# spice_test.net
KiCad netlist of a schematic drawn in EAGLE
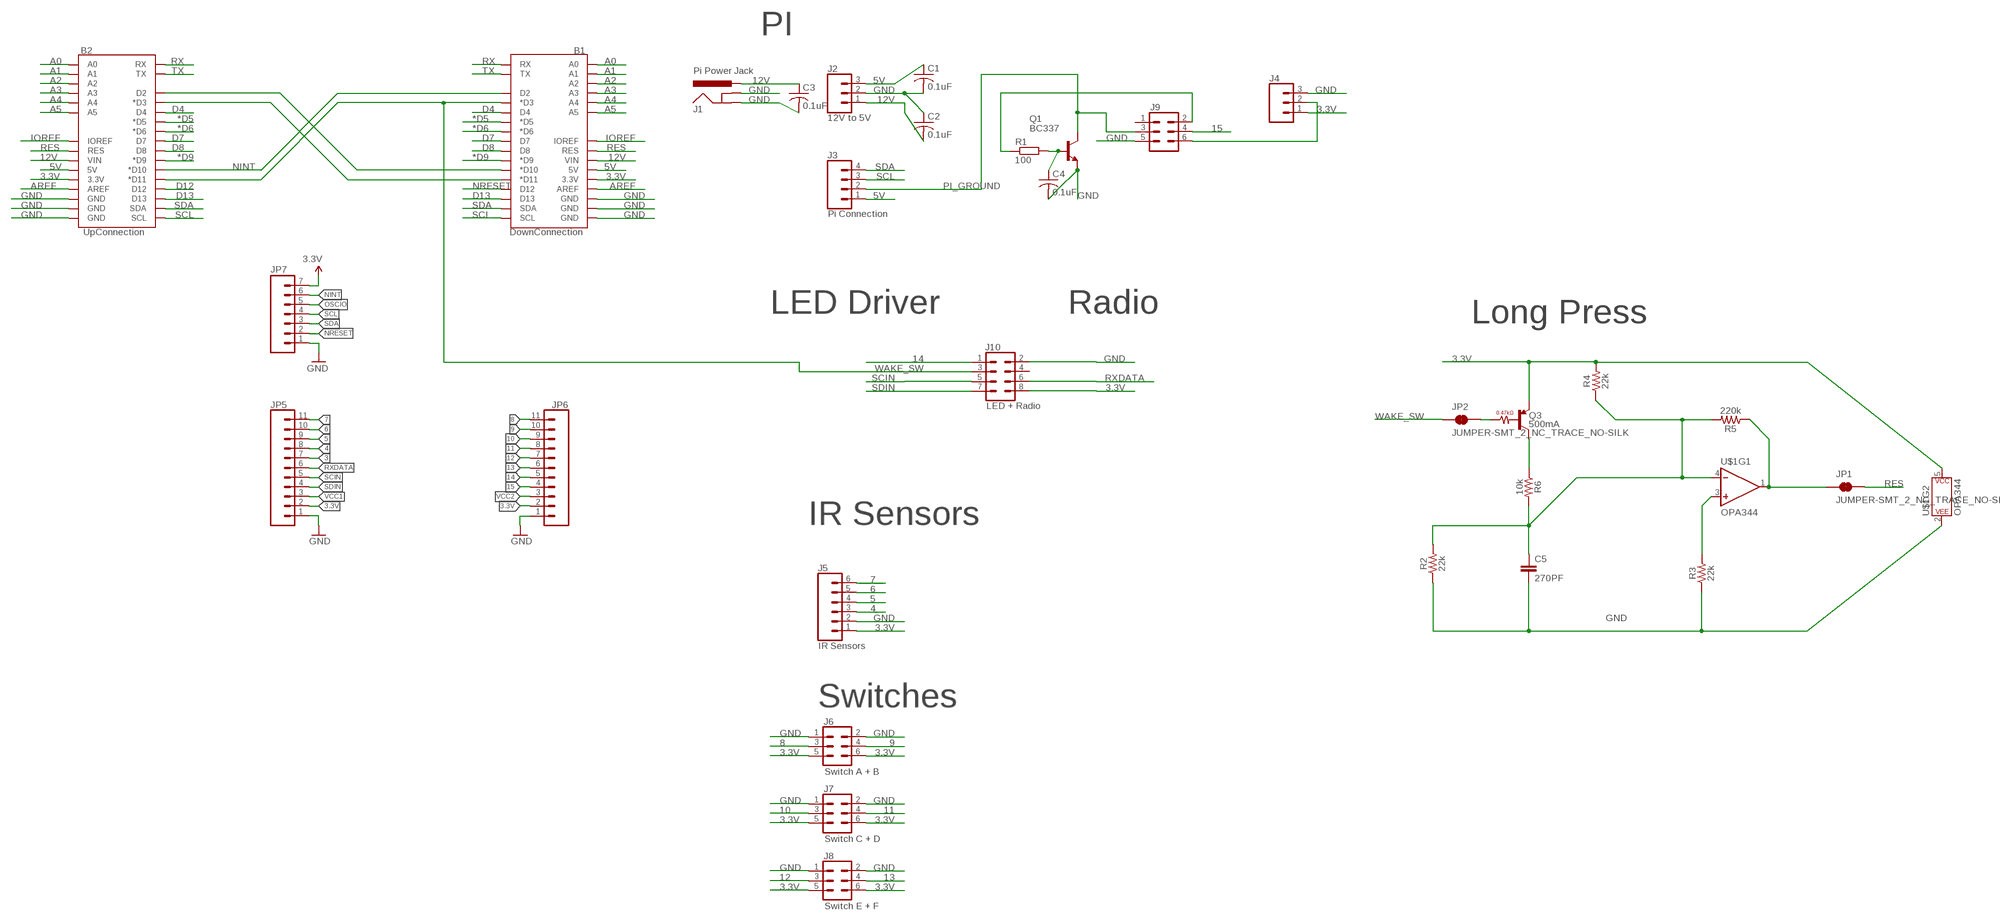
[diagram p0: schematic, sheet 1]

(export (version "E")
  (design (tool "Eeschema 10.0.6"))
  (components
    (comp (ref "B1")
      (value "DownConnection")
      (footprint "eagle-import:UNO_R3_SHIELD_NOLABELS")
      (libsource (lib "eagle-import") (part "ARDUINO_UNO_R3_SHIELDNOLABELS"))
    )
    (comp (ref "B2")
      (value "UpConnection")
      (footprint "eagle-import:UNO_R3_SHIELD_NOLABELS")
      (libsource (lib "eagle-import") (part "ARDUINO_UNO_R3_SHIELDNOLABELS"))
    )
    (comp (ref "C1")
      (value "0.1uF")
      (footprint "eagle-import:C025-024X044")
      (libsource (lib "eagle-import") (part "C-US025-024X044"))
    )
    (comp (ref "C2")
      (value "0.1uF")
      (footprint "eagle-import:C025-024X044")
      (libsource (lib "eagle-import") (part "C-US025-024X044"))
    )
    (comp (ref "C3")
      (value "0.1uF")
      (footprint "eagle-import:C025-024X044")
      (libsource (lib "eagle-import") (part "C-US025-024X044"))
    )
    (comp (ref "C4")
      (value "0.1uF")
      (footprint "eagle-import:C025-024X044")
      (libsource (lib "eagle-import") (part "C-US025-024X044"))
    )
    (comp (ref "C5")
      (value "270PF")
      (footprint "eagle-import:0603")
      (fields (field (name "SPICEPREFIX") "C"))
      (libsource (lib "eagle-import") (part "270PF-0603-50V-5%"))
    )
    (comp (ref "J1")
      (value "Pi Power Jack")
      (footprint "eagle-import:POWER_JACK_PTH_BREAD")
      (libsource (lib "eagle-import") (part "POWER_JACKPTH_BREAD"))
    )
    (comp (ref "J2")
      (value "12V to 5V")
      (footprint "eagle-import:1X03")
      (libsource (lib "eagle-import") (part "CONN_03"))
    )
    (comp (ref "J3")
      (value "Pi Connection")
      (footprint "eagle-import:1X04")
      (libsource (lib "eagle-import") (part "CONN_04"))
    )
    (comp (ref "J4")
      (value "CONN_03")
      (footprint "eagle-import:1X03")
      (libsource (lib "eagle-import") (part "CONN_03"))
    )
    (comp (ref "J5")
      (value "IR Sensors")
      (footprint "eagle-import:1X06")
      (libsource (lib "eagle-import") (part "CONN_06SILK_FEMALE_PTH"))
    )
    (comp (ref "J6")
      (value "Switch A + B")
      (footprint "eagle-import:2X3")
      (libsource (lib "eagle-import") (part "CONN_03X2FEMALE"))
    )
    (comp (ref "J7")
      (value "Switch C + D")
      (footprint "eagle-import:2X3")
      (libsource (lib "eagle-import") (part "CONN_03X2FEMALE"))
    )
    (comp (ref "J8")
      (value "Switch E + F")
      (footprint "eagle-import:2X3")
      (libsource (lib "eagle-import") (part "CONN_03X2FEMALE"))
    )
    (comp (ref "J9")
      (value "CONN_03X2NO_SILK")
      (footprint "eagle-import:2X3-NS")
      (libsource (lib "eagle-import") (part "CONN_03X2NO_SILK"))
    )
    (comp (ref "J10")
      (value "LED + Radio")
      (footprint "eagle-import:2X4")
      (libsource (lib "eagle-import") (part "CONN_04X2"))
    )
    (comp (ref "JP1")
      (value "JUMPER-SMT_2_NC_TRACE_NO-SILK")
      (footprint "eagle-import:SMT-JUMPER_2_NC_TRACE_NO-SILK")
      (fields (field (name "SPICEPREFIX") "B"))
      (libsource (lib "eagle-import") (part "JUMPER-SMT_2_NC_TRACE_NO-SILK"))
    )
    (comp (ref "JP2")
      (value "JUMPER-SMT_2_NC_TRACE_NO-SILK")
      (footprint "eagle-import:SMT-JUMPER_2_NC_TRACE_NO-SILK")
      (fields (field (name "SPICEPREFIX") "B"))
      (libsource (lib "eagle-import") (part "JUMPER-SMT_2_NC_TRACE_NO-SILK"))
    )
    (comp (ref "JP5")
      (value "CONN_11")
      (footprint "eagle-import:1X11")
      (libsource (lib "eagle-import") (part "CONN_11"))
    )
    (comp (ref "JP6")
      (value "CONN_11")
      (footprint "eagle-import:1X11")
      (libsource (lib "eagle-import") (part "CONN_11"))
    )
    (comp (ref "JP7")
      (value "M07")
      (footprint "eagle-import:1X07")
      (libsource (lib "eagle-import") (part "M07"))
    )
    (comp (ref "Q1")
      (value "BC337")
      (footprint "eagle-import:TO92")
      (libsource (lib "eagle-import") (part "BC337"))
    )
    (comp (ref "Q3")
      (value "500mA")
      (footprint "eagle-import:SOT23-3")
      (fields (field (name "SPICEPREFIX") "Q"))
      (libsource (lib "eagle-import") (part "TRANS_PNP_RES-DDTB142TC"))
    )
    (comp (ref "R1")
      (value "100")
      (footprint "eagle-import:0204_7")
      (libsource (lib "eagle-import") (part "R0204/7"))
    )
    (comp (ref "R2")
      (value "22k")
      (footprint "eagle-import:0603")
      (fields (field (name "SPICEPREFIX") "R"))
      (libsource (lib "eagle-import") (part "22KOHM-0603-1/10W-1%"))
    )
    (comp (ref "R3")
      (value "22k")
      (footprint "eagle-import:0603")
      (fields (field (name "SPICEPREFIX") "R"))
      (libsource (lib "eagle-import") (part "22KOHM-0603-1/10W-1%"))
    )
    (comp (ref "R4")
      (value "22k")
      (footprint "eagle-import:0603")
      (fields (field (name "SPICEPREFIX") "R"))
      (libsource (lib "eagle-import") (part "22KOHM-0603-1/10W-1%"))
    )
    (comp (ref "R5")
      (value "220k")
      (footprint "eagle-import:0603")
      (fields (field (name "SPICEPREFIX") "R"))
      (libsource (lib "eagle-import") (part "220KOHM-0603-1/10W-1%"))
    )
    (comp (ref "R6")
      (value "10k")
      (footprint "eagle-import:0603")
      (fields (field (name "SPICEPREFIX") "R"))
      (libsource (lib "eagle-import") (part "10KOHM-0603-1/10W-1%"))
    )
    (comp (ref "U$1")
      (value "OPA344")
      (footprint "eagle-import:SOT23-5")
      (fields (field (name "SPICEPREFIX") "B"))
      (libsource (lib "eagle-import") (part "OPA344"))
    )
  )
  (nets
    (net (code "1") (name "/*D5") (class "Default")
      (node (ref "B1") (pin "D5") (pinfunction "*D5_D5") (pintype "bidirectional"))
      (node (ref "B2") (pin "D5") (pinfunction "*D5_D5") (pintype "bidirectional"))
    )
    (net (code "2") (name "/*D6") (class "Default")
      (node (ref "B1") (pin "D6") (pinfunction "*D6_D6") (pintype "bidirectional"))
      (node (ref "B2") (pin "D6") (pinfunction "*D6_D6") (pintype "bidirectional"))
    )
    (net (code "3") (name "/*D9") (class "Default")
      (node (ref "B1") (pin "D9") (pinfunction "*D9_D9") (pintype "bidirectional"))
      (node (ref "B2") (pin "D9") (pinfunction "*D9_D9") (pintype "bidirectional"))
    )
    (net (code "4") (name "/5V") (class "Default")
      (node (ref "B1") (pin "5V") (pinfunction "5V_5V") (pintype "bidirectional"))
      (node (ref "B2") (pin "5V") (pinfunction "5V_5V") (pintype "bidirectional"))
      (node (ref "C1") (pin "1") (pinfunction "1_1") (pintype "passive"))
      (node (ref "J2") (pin "3") (pinfunction "3_3") (pintype "passive"))
      (node (ref "J3") (pin "1") (pinfunction "1_1") (pintype "passive"))
    )
    (net (code "5") (name "/12V") (class "Default")
      (node (ref "B1") (pin "VIN") (pinfunction "VIN_VIN") (pintype "bidirectional"))
      (node (ref "B2") (pin "VIN") (pinfunction "VIN_VIN") (pintype "bidirectional"))
      (node (ref "C2") (pin "2") (pinfunction "2_2") (pintype "passive"))
      (node (ref "C3") (pin "1") (pinfunction "1_1") (pintype "passive"))
      (node (ref "J1") (pin "PWR") (pinfunction "PWR_PWR") (pintype "bidirectional"))
      (node (ref "J2") (pin "1") (pinfunction "1_1") (pintype "passive"))
    )
    (net (code "6") (name "/A0") (class "Default")
      (node (ref "B1") (pin "A0") (pinfunction "A0_A0") (pintype "bidirectional"))
      (node (ref "B2") (pin "A0") (pinfunction "A0_A0") (pintype "bidirectional"))
    )
    (net (code "7") (name "/A1") (class "Default")
      (node (ref "B1") (pin "A1") (pinfunction "A1_A1") (pintype "bidirectional"))
      (node (ref "B2") (pin "A1") (pinfunction "A1_A1") (pintype "bidirectional"))
    )
    (net (code "8") (name "/A2") (class "Default")
      (node (ref "B1") (pin "A2") (pinfunction "A2_A2") (pintype "bidirectional"))
      (node (ref "B2") (pin "A2") (pinfunction "A2_A2") (pintype "bidirectional"))
    )
    (net (code "9") (name "/A3") (class "Default")
      (node (ref "B1") (pin "A3") (pinfunction "A3_A3") (pintype "bidirectional"))
      (node (ref "B2") (pin "A3") (pinfunction "A3_A3") (pintype "bidirectional"))
    )
    (net (code "10") (name "/A4") (class "Default")
      (node (ref "B1") (pin "A4") (pinfunction "A4_A4") (pintype "bidirectional"))
      (node (ref "B2") (pin "A4") (pinfunction "A4_A4") (pintype "bidirectional"))
    )
    (net (code "11") (name "/A5") (class "Default")
      (node (ref "B1") (pin "A5") (pinfunction "A5_A5") (pintype "bidirectional"))
      (node (ref "B2") (pin "A5") (pinfunction "A5_A5") (pintype "bidirectional"))
    )
    (net (code "12") (name "/AREF") (class "Default")
      (node (ref "B1") (pin "AREF") (pinfunction "AREF_AREF") (pintype "bidirectional"))
      (node (ref "B2") (pin "AREF") (pinfunction "AREF_AREF") (pintype "bidirectional"))
    )
    (net (code "13") (name "/D4") (class "Default")
      (node (ref "B1") (pin "D4") (pinfunction "D4_D4") (pintype "bidirectional"))
      (node (ref "B2") (pin "D4") (pinfunction "D4_D4") (pintype "bidirectional"))
    )
    (net (code "14") (name "/D7") (class "Default")
      (node (ref "B1") (pin "D7") (pinfunction "D7_D7") (pintype "bidirectional"))
      (node (ref "B2") (pin "D7") (pinfunction "D7_D7") (pintype "bidirectional"))
    )
    (net (code "15") (name "/D8") (class "Default")
      (node (ref "B1") (pin "D8") (pinfunction "D8_D8") (pintype "bidirectional"))
      (node (ref "B2") (pin "D8") (pinfunction "D8_D8") (pintype "bidirectional"))
    )
    (net (code "16") (name "/D12") (class "Default")
      (node (ref "B2") (pin "D12") (pinfunction "D12_D12") (pintype "bidirectional"))
    )
    (net (code "17") (name "/D13") (class "Default")
      (node (ref "B1") (pin "D13") (pinfunction "D13_D13") (pintype "bidirectional"))
      (node (ref "B2") (pin "D13") (pinfunction "D13_D13") (pintype "bidirectional"))
    )
    (net (code "18") (name "/IOREF") (class "Default")
      (node (ref "B1") (pin "IOREF") (pinfunction "IOREF_IOREF") (pintype "bidirectional"))
      (node (ref "B2") (pin "IOREF") (pinfunction "IOREF_IOREF") (pintype "bidirectional"))
    )
    (net (code "19") (name "/PI_GROUND") (class "Default")
      (node (ref "J3") (pin "2") (pinfunction "2_2") (pintype "passive"))
      (node (ref "J9") (pin "3") (pinfunction "3_3") (pintype "bidirectional"))
      (node (ref "Q1") (pin "3") (pinfunction "C_3") (pintype "passive"))
    )
    (net (code "20") (name "/RES") (class "Default")
      (node (ref "B1") (pin "RES") (pinfunction "RES_RES") (pintype "bidirectional"))
      (node (ref "B2") (pin "RES") (pinfunction "RES_RES") (pintype "bidirectional"))
      (node (ref "JP1") (pin "2") (pinfunction "2_2") (pintype "passive"))
    )
    (net (code "21") (name "/RX") (class "Default")
      (node (ref "B1") (pin "RX") (pinfunction "RX_RX") (pintype "bidirectional"))
      (node (ref "B2") (pin "RX") (pinfunction "RX_RX") (pintype "bidirectional"))
    )
    (net (code "22") (name "/TX") (class "Default")
      (node (ref "B1") (pin "TX") (pinfunction "TX_TX") (pintype "bidirectional"))
      (node (ref "B2") (pin "TX") (pinfunction "TX_TX") (pintype "bidirectional"))
    )
    (net (code "23") (name "/WAKE_SW") (class "Default")
      (node (ref "B1") (pin "D3") (pinfunction "*D3_D3") (pintype "bidirectional"))
      (node (ref "B2") (pin "D11") (pinfunction "*D11_D11") (pintype "bidirectional"))
      (node (ref "J10") (pin "3") (pinfunction "3_3") (pintype "passive"))
      (node (ref "JP2") (pin "1") (pinfunction "1_1") (pintype "passive"))
    )
    (net (code "24") (name "3") (class "Default")
      (node (ref "JP5") (pin "7") (pinfunction "7_7") (pintype "passive"))
    )
    (net (code "25") (name "3.3V") (class "Default")
      (node (ref "B1") (pin "3.3V") (pinfunction "3.3V_3.3V") (pintype "bidirectional"))
      (node (ref "B2") (pin "3.3V") (pinfunction "3.3V_3.3V") (pintype "bidirectional"))
      (node (ref "J10") (pin "8") (pinfunction "8_8") (pintype "passive"))
      (node (ref "J4") (pin "1") (pinfunction "1_1") (pintype "passive"))
      (node (ref "J5") (pin "1") (pinfunction "1_1") (pintype "passive"))
      (node (ref "J6") (pin "5") (pinfunction "5_5") (pintype "bidirectional"))
      (node (ref "J6") (pin "6") (pinfunction "6_6") (pintype "bidirectional"))
      (node (ref "J7") (pin "5") (pinfunction "5_5") (pintype "bidirectional"))
      (node (ref "J7") (pin "6") (pinfunction "6_6") (pintype "bidirectional"))
      (node (ref "J8") (pin "5") (pinfunction "5_5") (pintype "bidirectional"))
      (node (ref "J8") (pin "6") (pinfunction "6_6") (pintype "bidirectional"))
      (node (ref "JP5") (pin "2") (pinfunction "2_2") (pintype "passive"))
      (node (ref "JP6") (pin "2") (pinfunction "2_2") (pintype "passive"))
      (node (ref "JP7") (pin "7") (pinfunction "7_7") (pintype "passive"))
      (node (ref "Q3") (pin "2") (pinfunction "E_2") (pintype "passive"))
      (node (ref "R4") (pin "2") (pinfunction "2_2") (pintype "passive"))
      (node (ref "U$1") (pin "5") (pinfunction "P$V+_5") (pintype "bidirectional"))
    )
    (net (code "26") (name "4") (class "Default")
      (node (ref "J5") (pin "3") (pinfunction "3_3") (pintype "passive"))
      (node (ref "JP5") (pin "8") (pinfunction "8_8") (pintype "passive"))
    )
    (net (code "27") (name "5") (class "Default")
      (node (ref "J5") (pin "4") (pinfunction "4_4") (pintype "passive"))
      (node (ref "JP5") (pin "9") (pinfunction "9_9") (pintype "passive"))
    )
    (net (code "28") (name "6") (class "Default")
      (node (ref "J5") (pin "5") (pinfunction "5_5") (pintype "passive"))
      (node (ref "JP5") (pin "10") (pinfunction "10_10") (pintype "passive"))
    )
    (net (code "29") (name "7") (class "Default")
      (node (ref "J5") (pin "6") (pinfunction "6_6") (pintype "passive"))
      (node (ref "JP5") (pin "11") (pinfunction "11_11") (pintype "passive"))
    )
    (net (code "30") (name "8") (class "Default")
      (node (ref "J6") (pin "3") (pinfunction "3_3") (pintype "bidirectional"))
      (node (ref "JP6") (pin "11") (pinfunction "11_11") (pintype "passive"))
    )
    (net (code "31") (name "9") (class "Default")
      (node (ref "J6") (pin "4") (pinfunction "4_4") (pintype "bidirectional"))
      (node (ref "JP6") (pin "10") (pinfunction "10_10") (pintype "passive"))
    )
    (net (code "32") (name "10") (class "Default")
      (node (ref "J7") (pin "3") (pinfunction "3_3") (pintype "bidirectional"))
      (node (ref "JP6") (pin "9") (pinfunction "9_9") (pintype "passive"))
    )
    (net (code "33") (name "11") (class "Default")
      (node (ref "J7") (pin "4") (pinfunction "4_4") (pintype "bidirectional"))
      (node (ref "JP6") (pin "8") (pinfunction "8_8") (pintype "passive"))
    )
    (net (code "34") (name "12") (class "Default")
      (node (ref "J8") (pin "3") (pinfunction "3_3") (pintype "bidirectional"))
      (node (ref "JP6") (pin "7") (pinfunction "7_7") (pintype "passive"))
    )
    (net (code "35") (name "13") (class "Default")
      (node (ref "J8") (pin "4") (pinfunction "4_4") (pintype "bidirectional"))
      (node (ref "JP6") (pin "6") (pinfunction "6_6") (pintype "passive"))
    )
    (net (code "36") (name "14") (class "Default")
      (node (ref "J10") (pin "1") (pinfunction "1_1") (pintype "passive"))
      (node (ref "JP6") (pin "5") (pinfunction "5_5") (pintype "passive"))
    )
    (net (code "37") (name "15") (class "Default")
      (node (ref "J9") (pin "4") (pinfunction "4_4") (pintype "bidirectional"))
      (node (ref "JP6") (pin "4") (pinfunction "4_4") (pintype "passive"))
    )
    (net (code "38") (name "GND") (class "Default")
      (node (ref "B1") (pin "GND@0") (pinfunction "GND_GND@0") (pintype "bidirectional"))
      (node (ref "B1") (pin "GND@1") (pinfunction "GND_GND@1") (pintype "bidirectional"))
      (node (ref "B1") (pin "GND@2") (pinfunction "GND_GND@2") (pintype "bidirectional"))
      (node (ref "B2") (pin "GND@0") (pinfunction "GND_GND@0") (pintype "bidirectional"))
      (node (ref "B2") (pin "GND@1") (pinfunction "GND_GND@1") (pintype "bidirectional"))
      (node (ref "B2") (pin "GND@2") (pinfunction "GND_GND@2") (pintype "bidirectional"))
      (node (ref "C1") (pin "2") (pinfunction "2_2") (pintype "passive"))
      (node (ref "C2") (pin "1") (pinfunction "1_1") (pintype "passive"))
      (node (ref "C3") (pin "2") (pinfunction "2_2") (pintype "passive"))
      (node (ref "C4") (pin "2") (pinfunction "2_2") (pintype "passive"))
      (node (ref "C5") (pin "2") (pinfunction "2_2") (pintype "passive"))
      (node (ref "J1") (pin "GND") (pinfunction "GND_GND") (pintype "bidirectional"))
      (node (ref "J1") (pin "GNDBREAK") (pinfunction "GNDBREAK_GNDBREAK") (pintype "bidirectional"))
      (node (ref "J10") (pin "2") (pinfunction "2_2") (pintype "passive"))
      (node (ref "J2") (pin "2") (pinfunction "2_2") (pintype "passive"))
      (node (ref "J4") (pin "3") (pinfunction "3_3") (pintype "passive"))
      (node (ref "J5") (pin "2") (pinfunction "2_2") (pintype "passive"))
      (node (ref "J6") (pin "1") (pinfunction "1_1") (pintype "bidirectional"))
      (node (ref "J6") (pin "2") (pinfunction "2_2") (pintype "bidirectional"))
      (node (ref "J7") (pin "1") (pinfunction "1_1") (pintype "bidirectional"))
      (node (ref "J7") (pin "2") (pinfunction "2_2") (pintype "bidirectional"))
      (node (ref "J8") (pin "1") (pinfunction "1_1") (pintype "bidirectional"))
      (node (ref "J8") (pin "2") (pinfunction "2_2") (pintype "bidirectional"))
      (node (ref "J9") (pin "5") (pinfunction "5_5") (pintype "bidirectional"))
      (node (ref "JP5") (pin "1") (pinfunction "1_1") (pintype "passive"))
      (node (ref "JP6") (pin "1") (pinfunction "1_1") (pintype "passive"))
      (node (ref "JP7") (pin "1") (pinfunction "1_1") (pintype "passive"))
      (node (ref "Q1") (pin "1") (pinfunction "E_1") (pintype "passive"))
      (node (ref "R2") (pin "1") (pinfunction "1_1") (pintype "passive"))
      (node (ref "R3") (pin "1") (pinfunction "1_1") (pintype "passive"))
      (node (ref "U$1") (pin "2") (pinfunction "P$V-_2") (pintype "bidirectional"))
    )
    (net (code "39") (name "NINT") (class "Default")
      (node (ref "B1") (pin "D2") (pinfunction "D2_D2") (pintype "bidirectional"))
      (node (ref "B2") (pin "D10") (pinfunction "*D10_D10") (pintype "bidirectional"))
      (node (ref "JP7") (pin "6") (pinfunction "6_6") (pintype "passive"))
    )
    (net (code "40") (name "NRESET") (class "Default")
      (node (ref "B1") (pin "D12") (pinfunction "D12_D12") (pintype "bidirectional"))
      (node (ref "JP7") (pin "2") (pinfunction "2_2") (pintype "passive"))
    )
    (net (code "41") (name "Net-(B1-*D10)") (class "Default")
      (node (ref "B1") (pin "D10") (pinfunction "*D10_D10") (pintype "bidirectional"))
      (node (ref "B2") (pin "D2") (pinfunction "D2_D2") (pintype "bidirectional"))
    )
    (net (code "42") (name "Net-(B1-*D11)") (class "Default")
      (node (ref "B1") (pin "D11") (pinfunction "*D11_D11") (pintype "bidirectional"))
      (node (ref "B2") (pin "D3") (pinfunction "*D3_D3") (pintype "bidirectional"))
    )
    (net (code "43") (name "Net-(J4-Pad2)") (class "Default")
      (node (ref "J4") (pin "2") (pinfunction "2_2") (pintype "passive"))
      (node (ref "J9") (pin "6") (pinfunction "6_6") (pintype "bidirectional"))
    )
    (net (code "44") (name "Net-(J9-Pad2)") (class "Default")
      (node (ref "J9") (pin "2") (pinfunction "2_2") (pintype "bidirectional"))
      (node (ref "R1") (pin "1") (pinfunction "1_1") (pintype "passive"))
    )
    (net (code "45") (name "Net-(Q1-B)") (class "Default")
      (node (ref "C4") (pin "1") (pinfunction "1_1") (pintype "passive"))
      (node (ref "Q1") (pin "2") (pinfunction "B_2") (pintype "passive"))
      (node (ref "R1") (pin "2") (pinfunction "2_2") (pintype "passive"))
    )
    (net (code "46") (name "Net-(Q3-B)") (class "Default")
      (node (ref "JP2") (pin "2") (pinfunction "2_2") (pintype "passive"))
      (node (ref "Q3") (pin "1") (pinfunction "B_1") (pintype "passive"))
    )
    (net (code "47") (name "Net-(Q3-C)") (class "Default")
      (node (ref "Q3") (pin "3") (pinfunction "C_3") (pintype "passive"))
      (node (ref "R6") (pin "1") (pinfunction "1_1") (pintype "passive"))
    )
    (net (code "48") (name "Net-(U$1A-+IN)") (class "Default")
      (node (ref "R3") (pin "2") (pinfunction "2_2") (pintype "passive"))
      (node (ref "U$1") (pin "3") (pinfunction "+IN_3") (pintype "input"))
    )
    (net (code "49") (name "Net-(U$1A--IN)") (class "Default")
      (node (ref "C5") (pin "1") (pinfunction "1_1") (pintype "passive"))
      (node (ref "R2") (pin "2") (pinfunction "2_2") (pintype "passive"))
      (node (ref "R4") (pin "1") (pinfunction "1_1") (pintype "passive"))
      (node (ref "R5") (pin "2") (pinfunction "2_2") (pintype "passive"))
      (node (ref "R6") (pin "2") (pinfunction "2_2") (pintype "passive"))
      (node (ref "U$1") (pin "4") (pinfunction "-IN_4") (pintype "input"))
    )
    (net (code "50") (name "Net-(U$1A-OUT)") (class "Default")
      (node (ref "JP1") (pin "1") (pinfunction "1_1") (pintype "passive"))
      (node (ref "R5") (pin "1") (pinfunction "1_1") (pintype "passive"))
      (node (ref "U$1") (pin "1") (pinfunction "OUT_1") (pintype "output"))
    )
    (net (code "51") (name "OSCIO") (class "Default")
      (node (ref "JP7") (pin "5") (pinfunction "5_5") (pintype "passive"))
    )
    (net (code "52") (name "RXDATA") (class "Default")
      (node (ref "J10") (pin "6") (pinfunction "6_6") (pintype "passive"))
      (node (ref "JP5") (pin "6") (pinfunction "6_6") (pintype "passive"))
    )
    (net (code "53") (name "SCIN") (class "Default")
      (node (ref "J10") (pin "5") (pinfunction "5_5") (pintype "passive"))
      (node (ref "JP5") (pin "5") (pinfunction "5_5") (pintype "passive"))
    )
    (net (code "54") (name "SCL") (class "Default")
      (node (ref "B1") (pin "SCL") (pinfunction "SCL_SCL") (pintype "bidirectional"))
      (node (ref "B2") (pin "SCL") (pinfunction "SCL_SCL") (pintype "bidirectional"))
      (node (ref "J3") (pin "3") (pinfunction "3_3") (pintype "passive"))
      (node (ref "JP7") (pin "4") (pinfunction "4_4") (pintype "passive"))
    )
    (net (code "55") (name "SDA") (class "Default")
      (node (ref "B1") (pin "SDA") (pinfunction "SDA_SDA") (pintype "bidirectional"))
      (node (ref "B2") (pin "SDA") (pinfunction "SDA_SDA") (pintype "bidirectional"))
      (node (ref "J3") (pin "4") (pinfunction "4_4") (pintype "passive"))
      (node (ref "JP7") (pin "3") (pinfunction "3_3") (pintype "passive"))
    )
    (net (code "56") (name "SDIN") (class "Default")
      (node (ref "J10") (pin "7") (pinfunction "7_7") (pintype "passive"))
      (node (ref "JP5") (pin "4") (pinfunction "4_4") (pintype "passive"))
    )
    (net (code "57") (name "VCC1") (class "Default")
      (node (ref "JP5") (pin "3") (pinfunction "3_3") (pintype "passive"))
    )
    (net (code "58") (name "VCC2") (class "Default")
      (node (ref "JP6") (pin "3") (pinfunction "3_3") (pintype "passive"))
    )
    (net (code "59") (name "unconnected-(J9-Pad1)") (class "Default")
      (node (ref "J9") (pin "1") (pinfunction "1_1") (pintype "bidirectional"))
    )
    (net (code "60") (name "unconnected-(J10-Pad4)") (class "Default")
      (node (ref "J10") (pin "4") (pinfunction "4_4") (pintype "passive"))
    )
  )
)
